# GPS.net
KiCad netlist of a schematic drawn in Altium Designer
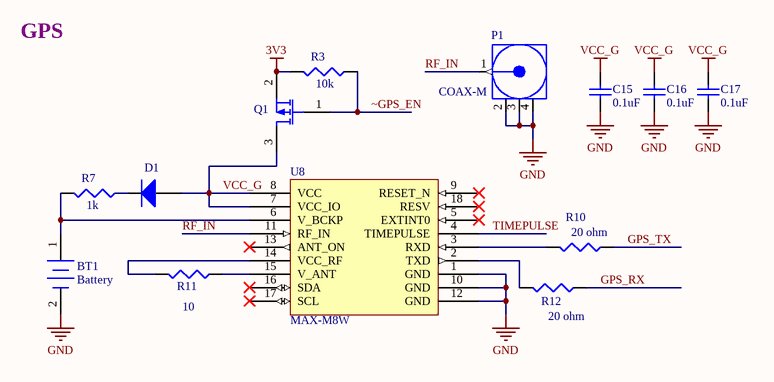
[diagram p0: GPS.SchDoc]

(export (version "E")
  (design (tool "Eeschema 10.0.6"))
  (components
    (comp (ref "BT1")
      (value "Battery")
      (footprint "Bat Antenna MS621FE-Fl11E")
      (description "Multicell Battery")
      (fields (field (name "PUBLISHER") "Altium Limited"))
      (libsource (lib "Miscellaneous Devices") (part "Battery"))
    )
    (comp (ref "C15")
      (value "0.1uF")
      (footprint "CAP_0603")
      (description "Capacitor (Semiconductor SIM Model)")
      (fields (field (name "Comment") "Cap Semi") (field (name "PUBLISHER") "Altium Limited"))
      (libsource (lib "Miscellaneous Devices") (part "Cap Semi"))
    )
    (comp (ref "C16")
      (value "0.1uF")
      (footprint "CAP_0603")
      (description "Capacitor (Semiconductor SIM Model)")
      (fields (field (name "Comment") "Cap Semi") (field (name "PUBLISHER") "Altium Limited"))
      (libsource (lib "Miscellaneous Devices") (part "Cap Semi"))
    )
    (comp (ref "C17")
      (value "0.1uF")
      (footprint "CAP_0603")
      (description "Capacitor (Semiconductor SIM Model)")
      (fields (field (name "Comment") "Cap Semi") (field (name "PUBLISHER") "Altium Limited"))
      (libsource (lib "Miscellaneous Devices") (part "Cap Semi"))
    )
    (comp (ref "D1")
      (value "~")
      (footprint "Diode(SOD-323 )")
      (description "Default Diode")
      (fields (field (name "PUBLISHER") "Altium Limited"))
      (libsource (lib "Miscellaneous Devices") (part "Diode"))
    )
    (comp (ref "P1")
      (value "COAX-M")
      (footprint "SMA Connector")
      (description "RF Coaxial PCB Connector, MMCX; Thru-Hole, Vertical Mount Plug,  50 Ohm Impedance")
      (fields (field (name "PUBLISHER") "Altium Limited"))
      (libsource (lib "Miscellaneous Connectors") (part "COAX-M"))
    )
    (comp (ref "Q1")
      (value "MOSFET-P")
      (footprint "P-MOS (SOT323)")
      (description "P-Channel MOSFET")
      (fields (field (name "PUBLISHER") "Altium Limited"))
      (libsource (lib "Miscellaneous Devices") (part "MOSFET-P"))
    )
    (comp (ref "R3")
      (value "10k")
      (footprint "generated_footprints:RES_0603")
      (description "Resistor")
      (fields (field (name "Comment") "Res3") (field (name "PUBLISHER") "Altium Limited"))
      (libsource (lib "Miscellaneous Devices") (part "Res3"))
    )
    (comp (ref "R7")
      (value "1k")
      (footprint "generated_footprints:RES_0603")
      (description "Resistor")
      (fields (field (name "Comment") "Res3") (field (name "PUBLISHER") "Altium Limited"))
      (libsource (lib "Miscellaneous Devices") (part "Res3"))
    )
    (comp (ref "R10")
      (value "20 ohm")
      (footprint "generated_footprints:RES_0603")
      (description "Resistor")
      (fields (field (name "Comment") "Res3") (field (name "PUBLISHER") "Altium Limited"))
      (libsource (lib "Miscellaneous Devices") (part "Res3"))
    )
    (comp (ref "R11")
      (value "10")
      (footprint "generated_footprints:RES_0603")
      (description "Resistor")
      (fields (field (name "Comment") "Res3") (field (name "PUBLISHER") "Altium Limited"))
      (libsource (lib "Miscellaneous Devices") (part "Res3"))
    )
    (comp (ref "R12")
      (value "20 ohm")
      (footprint "generated_footprints:RES_0603")
      (description "Resistor")
      (fields (field (name "Comment") "Res3") (field (name "PUBLISHER") "Altium Limited"))
      (libsource (lib "Miscellaneous Devices") (part "Res3"))
    )
    (comp (ref "U8") (value "MAX-M8W") (footprint "MAX-M8W") (libsource (lib "Components") (part "MAX-M8")))
  )
  (nets
    (net (code "1") (name "/GPS_RX") (class "Default")
      (node (ref "R12") (pin "1") (pinfunction "1_1") (pintype "power_in"))
    )
    (net (code "2") (name "/GPS_TX") (class "Default")
      (node (ref "R10") (pin "1") (pinfunction "1_1") (pintype "power_in"))
    )
    (net (code "3") (name "/RF_IN") (class "Default")
      (node (ref "P1") (pin "1") (pinfunction "Signal_1") (pintype "output"))
      (node (ref "U8") (pin "11") (pinfunction "RF_IN_11") (pintype "input"))
    )
    (net (code "4") (name "/TIMEPULSE") (class "Default")
      (node (ref "U8") (pin "4") (pinfunction "TIMEPULSE_4") (pintype "power_in"))
    )
    (net (code "5") (name "/~GPS_EN") (class "Default")
      (node (ref "Q1") (pin "1") (pinfunction "G_1") (pintype "passive"))
      (node (ref "R3") (pin "1") (pinfunction "1_1") (pintype "power_in"))
    )
    (net (code "6") (name "3V3") (class "Default")
      (node (ref "Q1") (pin "2") (pinfunction "S_2") (pintype "passive"))
      (node (ref "R3") (pin "2") (pinfunction "2_2") (pintype "power_in"))
    )
    (net (code "7") (name "GND") (class "Default")
      (node (ref "BT1") (pin "2") (pinfunction "-_2") (pintype "power_in"))
      (node (ref "C15") (pin "2") (pinfunction "2_2") (pintype "passive"))
      (node (ref "C16") (pin "2") (pinfunction "2_2") (pintype "passive"))
      (node (ref "C17") (pin "2") (pinfunction "2_2") (pintype "passive"))
      (node (ref "P1") (pin "2") (pinfunction "GND_2") (pintype "power_in"))
      (node (ref "P1") (pin "3") (pinfunction "GND_3") (pintype "power_in"))
      (node (ref "P1") (pin "4") (pinfunction "GND_4") (pintype "power_in"))
      (node (ref "U8") (pin "1") (pinfunction "GND_1") (pintype "power_in"))
      (node (ref "U8") (pin "10") (pinfunction "GND_10") (pintype "power_in"))
      (node (ref "U8") (pin "12") (pinfunction "GND_12") (pintype "power_in"))
    )
    (net (code "8") (name "Net-(BT1-+)") (class "Default")
      (node (ref "BT1") (pin "1") (pinfunction "+_1") (pintype "power_in"))
      (node (ref "R7") (pin "2") (pinfunction "2_2") (pintype "power_in"))
      (node (ref "U8") (pin "6") (pinfunction "V_BCKP_6") (pintype "power_in"))
    )
    (net (code "9") (name "Net-(D1-K)") (class "Default")
      (node (ref "D1") (pin "2") (pinfunction "K_2") (pintype "passive"))
      (node (ref "R7") (pin "1") (pinfunction "1_1") (pintype "power_in"))
    )
    (net (code "10") (name "Net-(U8-RXD)") (class "Default")
      (node (ref "R10") (pin "2") (pinfunction "2_2") (pintype "power_in"))
      (node (ref "U8") (pin "3") (pinfunction "RXD_3") (pintype "input"))
    )
    (net (code "11") (name "Net-(U8-TXD)") (class "Default")
      (node (ref "R12") (pin "2") (pinfunction "2_2") (pintype "power_in"))
      (node (ref "U8") (pin "2") (pinfunction "TXD_2") (pintype "output"))
    )
    (net (code "12") (name "Net-(U8-VCC_RF)") (class "Default")
      (node (ref "R11") (pin "2") (pinfunction "2_2") (pintype "power_in"))
      (node (ref "U8") (pin "14") (pinfunction "VCC_RF_14") (pintype "power_in"))
    )
    (net (code "13") (name "Net-(U8-V_ANT)") (class "Default")
      (node (ref "R11") (pin "1") (pinfunction "1_1") (pintype "power_in"))
      (node (ref "U8") (pin "15") (pinfunction "V_ANT_15") (pintype "power_in"))
    )
    (net (code "14") (name "VCC_G") (class "Default")
      (node (ref "C15") (pin "1") (pinfunction "1_1") (pintype "passive"))
      (node (ref "C16") (pin "1") (pinfunction "1_1") (pintype "passive"))
      (node (ref "C17") (pin "1") (pinfunction "1_1") (pintype "passive"))
      (node (ref "D1") (pin "1") (pinfunction "A_1") (pintype "passive"))
      (node (ref "Q1") (pin "3") (pinfunction "D_3") (pintype "passive"))
      (node (ref "U8") (pin "7") (pinfunction "VCC_IO_7") (pintype "power_in"))
      (node (ref "U8") (pin "8") (pinfunction "VCC_8") (pintype "power_in"))
    )
    (net (code "15") (name "unconnected-(U8-ANT_ON-Pad13)") (class "Default")
      (node (ref "U8") (pin "13") (pinfunction "ANT_ON_13") (pintype "output+no_connect"))
    )
    (net (code "16") (name "unconnected-(U8-EXTINT0-Pad5)") (class "Default")
      (node (ref "U8") (pin "5") (pinfunction "EXTINT0_5") (pintype "input+no_connect"))
    )
    (net (code "17") (name "unconnected-(U8-RESET_N-Pad9)") (class "Default")
      (node (ref "U8") (pin "9") (pinfunction "RESET_N_9") (pintype "input+no_connect"))
    )
    (net (code "18") (name "unconnected-(U8-RESV-Pad18)") (class "Default")
      (node (ref "U8") (pin "18") (pinfunction "RESV_18") (pintype "input+no_connect"))
    )
    (net (code "19") (name "unconnected-(U8-SCL-Pad17)") (class "Default")
      (node (ref "U8") (pin "17") (pinfunction "SCL_17") (pintype "bidirectional+no_connect"))
    )
    (net (code "20") (name "unconnected-(U8-SDA-Pad16)") (class "Default")
      (node (ref "U8") (pin "16") (pinfunction "SDA_16") (pintype "bidirectional+no_connect"))
    )
  )
)
